# main.net
KiCad netlist of a schematic drawn in EAGLE
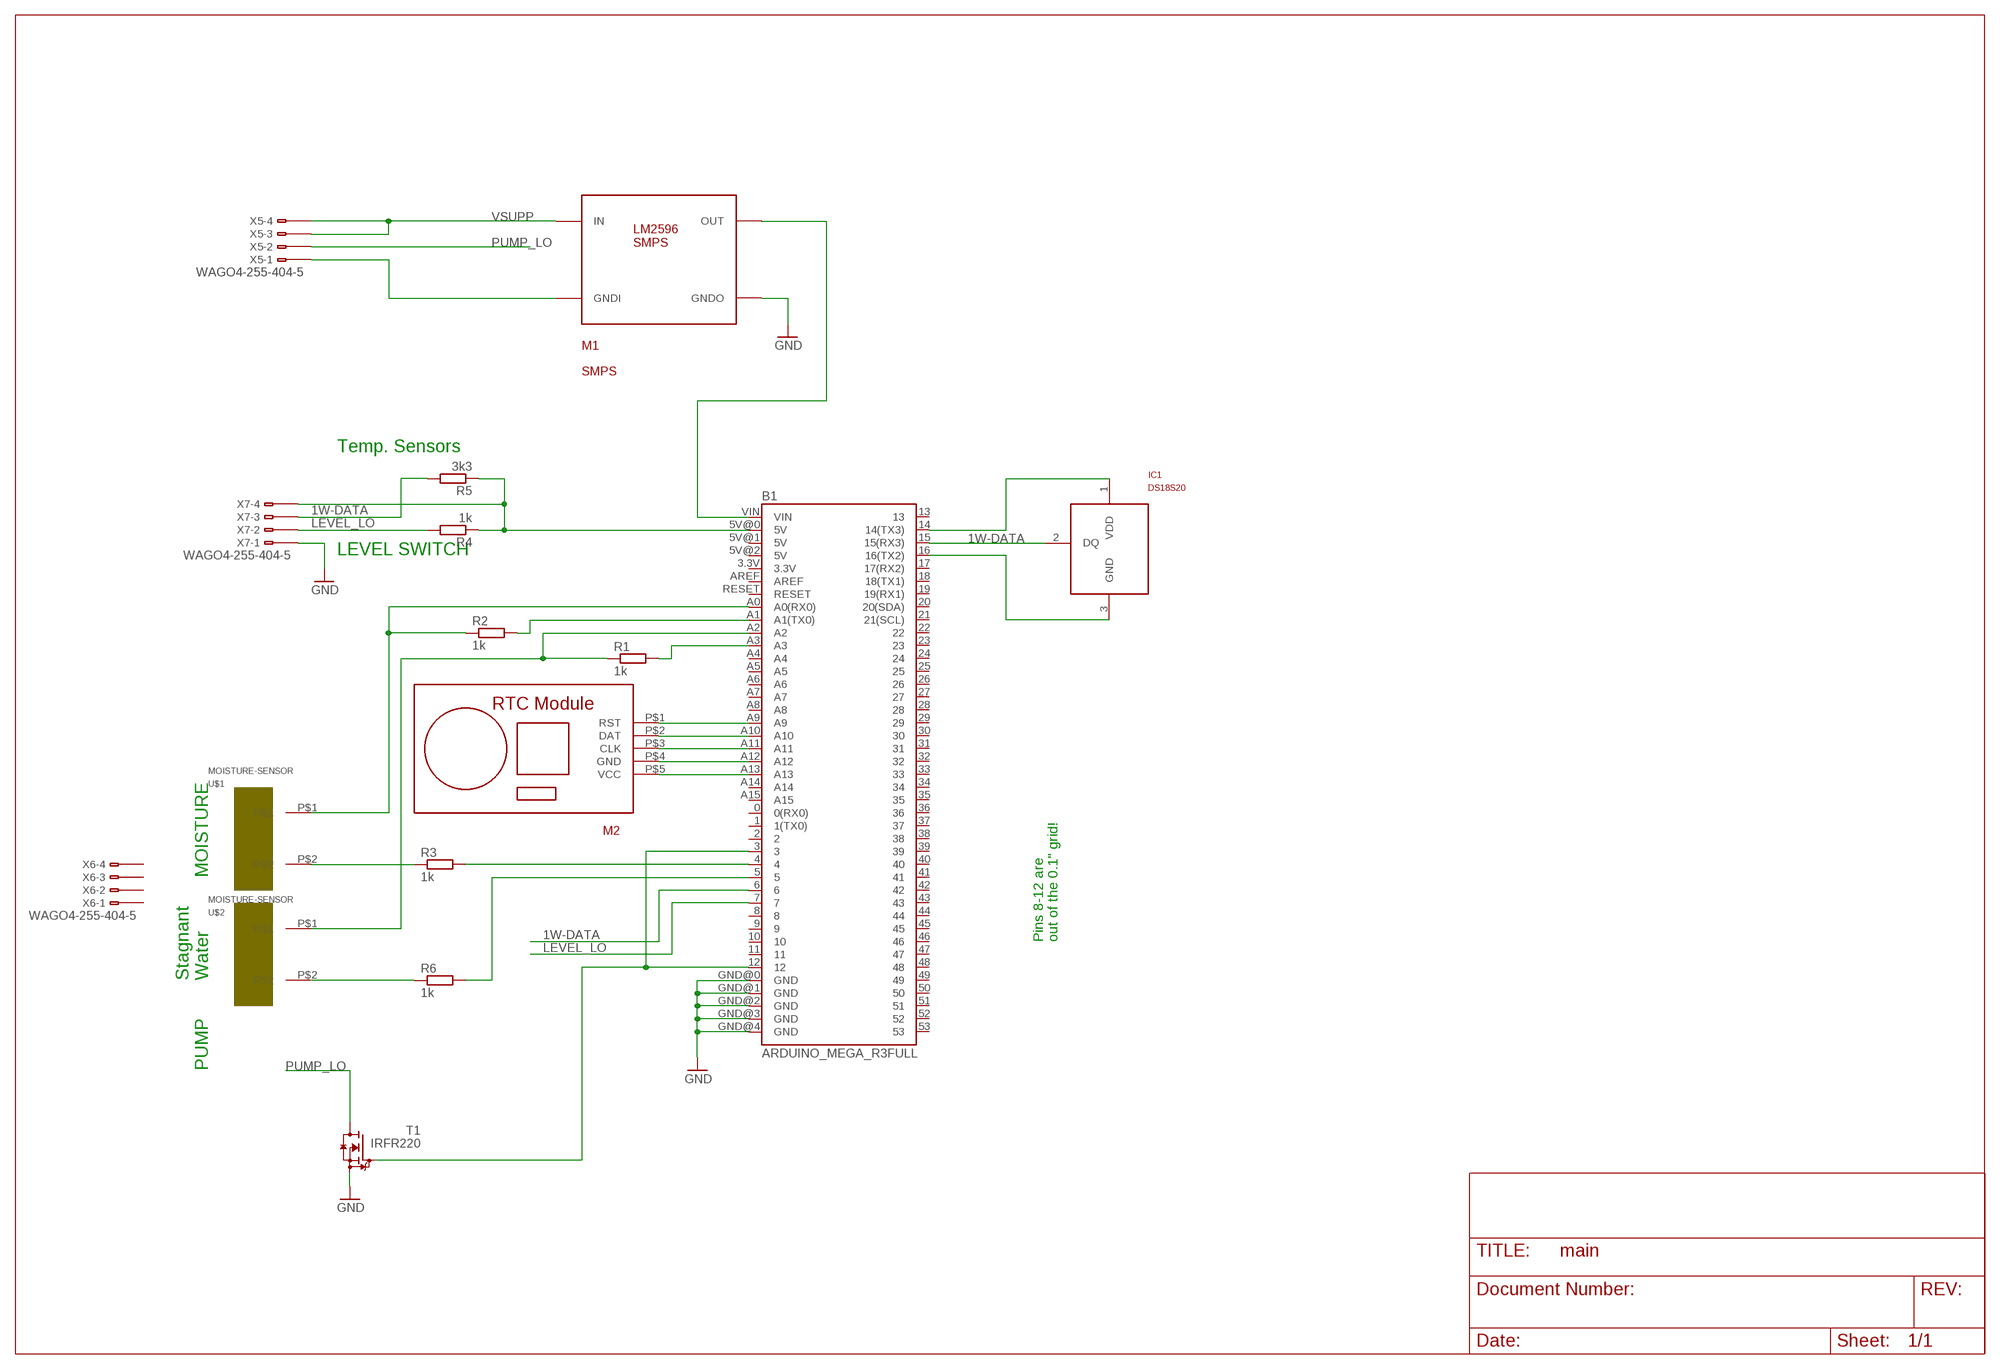
[diagram p0: schematic, sheet 1]

(export (version "E")
  (design (tool "Eeschema 10.0.6"))
  (components
    (comp (ref "B1")
      (value "ARDUINO_MEGA_R3FULL")
      (footprint "eagle-import:ARDUINO_MEGA")
      (libsource (lib "eagle-import") (part "ARDUINO_MEGA_R3FULL"))
    )
    (comp (ref "IC1")
      (value "DS18S20")
      (footprint "eagle-import:TO92-")
      (libsource (lib "eagle-import") (part "DS1820"))
    )
    (comp (ref "M1")
      (value "SMPS")
      (footprint "eagle-import:SMPS-1")
      (libsource (lib "eagle-import") (part "SMPS"))
    )
    (comp (ref "M2")
      (value "DS1302-MODULE")
      (footprint "eagle-import:DS1302-MOD")
      (libsource (lib "eagle-import") (part "DS1302-MODULE"))
    )
    (comp (ref "R1")
      (value "1k")
      (footprint "eagle-import:R0805")
      (libsource (lib "eagle-import") (part "R-EU_R0805"))
    )
    (comp (ref "R2")
      (value "1k")
      (footprint "eagle-import:R0805")
      (libsource (lib "eagle-import") (part "R-EU_R0805"))
    )
    (comp (ref "R3")
      (value "1k")
      (footprint "eagle-import:R0805")
      (libsource (lib "eagle-import") (part "R-EU_R0805"))
    )
    (comp (ref "R4")
      (value "1k")
      (footprint "eagle-import:R0805")
      (libsource (lib "eagle-import") (part "R-EU_R0805"))
    )
    (comp (ref "R5")
      (value "3k3")
      (footprint "eagle-import:R0805")
      (libsource (lib "eagle-import") (part "R-EU_R0805"))
    )
    (comp (ref "R6")
      (value "1k")
      (footprint "eagle-import:R0805")
      (libsource (lib "eagle-import") (part "R-EU_R0805"))
    )
    (comp (ref "T1")
      (value "IRFR220")
      (footprint "eagle-import:TO252")
      (libsource (lib "eagle-import") (part "IRFR220"))
    )
    (comp (ref "U$1")
      (value "MOISTURE-SENSOR")
      (footprint "eagle-import:MOISTURE-SENSOR")
      (libsource (lib "eagle-import") (part "MOISTURE-SENSOR"))
    )
    (comp (ref "U$2")
      (value "MOISTURE-SENSOR")
      (footprint "eagle-import:MOISTURE-SENSOR")
      (libsource (lib "eagle-import") (part "MOISTURE-SENSOR"))
    )
    (comp (ref "X5")
      (value "WAGO4-255-404-5")
      (footprint "eagle-import:255-404-5")
      (fields (field (name "MPN") "255-404"))
      (libsource (lib "eagle-import") (part "WAGO4-255-404-5"))
    )
    (comp (ref "X6")
      (value "WAGO4-255-404-5")
      (footprint "eagle-import:255-404-5")
      (fields (field (name "MPN") "255-404"))
      (libsource (lib "eagle-import") (part "WAGO4-255-404-5"))
    )
    (comp (ref "X7")
      (value "WAGO4-255-404-5")
      (footprint "eagle-import:255-404-5")
      (fields (field (name "MPN") "255-404"))
      (libsource (lib "eagle-import") (part "WAGO4-255-404-5"))
    )
  )
  (nets
    (net (code "1") (name "/1W-DATA") (class "Default")
      (node (ref "B1") (pin "15") (pinfunction "15(RX3)_15") (pintype "bidirectional"))
      (node (ref "B1") (pin "6") (pinfunction "6_6") (pintype "bidirectional"))
      (node (ref "IC1") (pin "2") (pinfunction "DQ_2") (pintype "bidirectional"))
      (node (ref "R5") (pin "2") (pinfunction "2_2") (pintype "passive"))
      (node (ref "X7") (pin "B3") (pinfunction "B1_B3") (pintype "passive"))
    )
    (net (code "2") (name "/LEVEL_LO") (class "Default")
      (node (ref "B1") (pin "7") (pinfunction "7_7") (pintype "bidirectional"))
      (node (ref "R4") (pin "2") (pinfunction "2_2") (pintype "passive"))
      (node (ref "X7") (pin "B2") (pinfunction "B1_B2") (pintype "passive"))
    )
    (net (code "3") (name "/PUMP_LO") (class "Default")
      (node (ref "T1") (pin "3") (pinfunction "D_3") (pintype "passive"))
      (node (ref "X5") (pin "B2") (pinfunction "B1_B2") (pintype "passive"))
    )
    (net (code "4") (name "/VSUPP") (class "Default")
      (node (ref "M1") (pin "P$3") (pinfunction "IN_P$3") (pintype "input"))
      (node (ref "M1") (pin "P$4") (pinfunction "IN_P$4") (pintype "input"))
      (node (ref "X5") (pin "B3") (pinfunction "B1_B3") (pintype "passive"))
      (node (ref "X5") (pin "B4") (pinfunction "B1_B4") (pintype "passive"))
    )
    (net (code "5") (name "GND") (class "Default")
      (node (ref "B1") (pin "GND@0") (pinfunction "GND_GND@0") (pintype "bidirectional"))
      (node (ref "B1") (pin "GND@1") (pinfunction "GND_GND@1") (pintype "bidirectional"))
      (node (ref "B1") (pin "GND@2") (pinfunction "GND_GND@2") (pintype "bidirectional"))
      (node (ref "B1") (pin "GND@3") (pinfunction "GND_GND@3") (pintype "bidirectional"))
      (node (ref "B1") (pin "GND@4") (pinfunction "GND_GND@4") (pintype "bidirectional"))
      (node (ref "M1") (pin "P$5") (pinfunction "GNDO_P$5") (pintype "output"))
      (node (ref "M1") (pin "P$6") (pinfunction "GNDO_P$6") (pintype "output"))
      (node (ref "T1") (pin "2") (pinfunction "S_2") (pintype "passive"))
      (node (ref "X7") (pin "B1") (pinfunction "B1_B1") (pintype "passive"))
    )
    (net (code "6") (name "Net-(B1-14(TX3))") (class "Default")
      (node (ref "B1") (pin "14") (pinfunction "14(TX3)_14") (pintype "bidirectional"))
      (node (ref "IC1") (pin "1") (pinfunction "VDD_1") (pintype "bidirectional"))
    )
    (net (code "7") (name "Net-(B1-16(TX2))") (class "Default")
      (node (ref "B1") (pin "16") (pinfunction "16(TX2)_16") (pintype "bidirectional"))
      (node (ref "IC1") (pin "3") (pinfunction "GND_3") (pintype "bidirectional"))
    )
    (net (code "8") (name "Net-(B1-A0(RX0))") (class "Default")
      (node (ref "B1") (pin "A0") (pinfunction "A0(RX0)_A0") (pintype "bidirectional"))
      (node (ref "R2") (pin "1") (pinfunction "1_1") (pintype "passive"))
      (node (ref "U$1") (pin "P$1") (pinfunction "P$1_P$1") (pintype "bidirectional"))
    )
    (net (code "9") (name "Net-(B1-A1(TX0))") (class "Default")
      (node (ref "B1") (pin "A1") (pinfunction "A1(TX0)_A1") (pintype "bidirectional"))
      (node (ref "R2") (pin "2") (pinfunction "2_2") (pintype "passive"))
    )
    (net (code "10") (name "Net-(B1-Pad4)") (class "Default")
      (node (ref "B1") (pin "4") (pinfunction "4_4") (pintype "bidirectional"))
      (node (ref "R3") (pin "2") (pinfunction "2_2") (pintype "passive"))
    )
    (net (code "11") (name "Net-(B1-Pad5)") (class "Default")
      (node (ref "B1") (pin "5") (pinfunction "5_5") (pintype "bidirectional"))
      (node (ref "R6") (pin "2") (pinfunction "2_2") (pintype "passive"))
    )
    (net (code "12") (name "Net-(B1-PadA2)") (class "Default")
      (node (ref "B1") (pin "A2") (pinfunction "A2_A2") (pintype "bidirectional"))
      (node (ref "R1") (pin "1") (pinfunction "1_1") (pintype "passive"))
      (node (ref "U$2") (pin "P$1") (pinfunction "P$1_P$1") (pintype "bidirectional"))
    )
    (net (code "13") (name "Net-(B1-PadA3)") (class "Default")
      (node (ref "B1") (pin "A3") (pinfunction "A3_A3") (pintype "bidirectional"))
      (node (ref "R1") (pin "2") (pinfunction "2_2") (pintype "passive"))
    )
    (net (code "14") (name "Net-(B1-PadVIN)") (class "Default")
      (node (ref "B1") (pin "VIN") (pinfunction "VIN_VIN") (pintype "bidirectional"))
      (node (ref "M1") (pin "P$7") (pinfunction "OUT_P$7") (pintype "output"))
      (node (ref "M1") (pin "P$8") (pinfunction "OUT_P$8") (pintype "output"))
    )
    (net (code "15") (name "Net-(M1-GNDI-PadP$1)") (class "Default")
      (node (ref "M1") (pin "P$1") (pinfunction "GNDI_P$1") (pintype "input"))
      (node (ref "M1") (pin "P$2") (pinfunction "GNDI_P$2") (pintype "input"))
      (node (ref "X5") (pin "B1") (pinfunction "B1_B1") (pintype "passive"))
    )
    (net (code "16") (name "Net-(M2-CLK)") (class "Default")
      (node (ref "B1") (pin "A11") (pinfunction "A11_A11") (pintype "bidirectional"))
      (node (ref "M2") (pin "P$3") (pinfunction "CLK_P$3") (pintype "bidirectional"))
    )
    (net (code "17") (name "Net-(M2-DAT)") (class "Default")
      (node (ref "B1") (pin "A10") (pinfunction "A10_A10") (pintype "bidirectional"))
      (node (ref "M2") (pin "P$2") (pinfunction "DAT_P$2") (pintype "bidirectional"))
    )
    (net (code "18") (name "Net-(M2-GND)") (class "Default")
      (node (ref "B1") (pin "A12") (pinfunction "A12_A12") (pintype "bidirectional"))
      (node (ref "M2") (pin "P$4") (pinfunction "GND_P$4") (pintype "bidirectional"))
    )
    (net (code "19") (name "Net-(M2-RST)") (class "Default")
      (node (ref "B1") (pin "A9") (pinfunction "A9_A9") (pintype "bidirectional"))
      (node (ref "M2") (pin "P$1") (pinfunction "RST_P$1") (pintype "bidirectional"))
    )
    (net (code "20") (name "Net-(M2-VCC)") (class "Default")
      (node (ref "B1") (pin "A13") (pinfunction "A13_A13") (pintype "bidirectional"))
      (node (ref "M2") (pin "P$5") (pinfunction "VCC_P$5") (pintype "bidirectional"))
    )
    (net (code "21") (name "Net-(R3-Pad1)") (class "Default")
      (node (ref "R3") (pin "1") (pinfunction "1_1") (pintype "passive"))
      (node (ref "U$1") (pin "P$2") (pinfunction "P$2_P$2") (pintype "bidirectional"))
    )
    (net (code "22") (name "Net-(R6-Pad1)") (class "Default")
      (node (ref "R6") (pin "1") (pinfunction "1_1") (pintype "passive"))
      (node (ref "U$2") (pin "P$2") (pinfunction "P$2_P$2") (pintype "bidirectional"))
    )
    (net (code "23") (name "Net-(T1-G)") (class "Default")
      (node (ref "B1") (pin "12") (pinfunction "12_12") (pintype "bidirectional"))
      (node (ref "B1") (pin "3") (pinfunction "3_3") (pintype "bidirectional"))
      (node (ref "T1") (pin "1") (pinfunction "G_1") (pintype "passive"))
    )
    (net (code "24") (name "Net-(X7D-B1)") (class "Default")
      (node (ref "B1") (pin "5V@0") (pinfunction "5V_5V@0") (pintype "bidirectional"))
      (node (ref "R4") (pin "1") (pinfunction "1_1") (pintype "passive"))
      (node (ref "R5") (pin "1") (pinfunction "1_1") (pintype "passive"))
      (node (ref "X7") (pin "B4") (pinfunction "B1_B4") (pintype "passive"))
    )
    (net (code "25") (name "unconnected-(B1-0(RX0)-Pad0)") (class "Default")
      (node (ref "B1") (pin "0") (pinfunction "0(RX0)_0") (pintype "bidirectional"))
    )
    (net (code "26") (name "unconnected-(B1-1(TX0)-Pad1)") (class "Default")
      (node (ref "B1") (pin "1") (pinfunction "1(TX0)_1") (pintype "bidirectional"))
    )
    (net (code "27") (name "unconnected-(B1-5V-Pad5V@1)") (class "Default")
      (node (ref "B1") (pin "5V@1") (pinfunction "5V_5V@1") (pintype "bidirectional"))
    )
    (net (code "28") (name "unconnected-(B1-5V-Pad5V@2)") (class "Default")
      (node (ref "B1") (pin "5V@2") (pinfunction "5V_5V@2") (pintype "bidirectional"))
    )
    (net (code "29") (name "unconnected-(B1-17(RX2)-Pad17)") (class "Default")
      (node (ref "B1") (pin "17") (pinfunction "17(RX2)_17") (pintype "bidirectional"))
    )
    (net (code "30") (name "unconnected-(B1-18(TX1)-Pad18)") (class "Default")
      (node (ref "B1") (pin "18") (pinfunction "18(TX1)_18") (pintype "bidirectional"))
    )
    (net (code "31") (name "unconnected-(B1-19(RX1)-Pad19)") (class "Default")
      (node (ref "B1") (pin "19") (pinfunction "19(RX1)_19") (pintype "bidirectional"))
    )
    (net (code "32") (name "unconnected-(B1-20(SDA)-Pad20)") (class "Default")
      (node (ref "B1") (pin "20") (pinfunction "20(SDA)_20") (pintype "bidirectional"))
    )
    (net (code "33") (name "unconnected-(B1-21(SCL)-Pad21)") (class "Default")
      (node (ref "B1") (pin "21") (pinfunction "21(SCL)_21") (pintype "bidirectional"))
    )
    (net (code "34") (name "unconnected-(B1-Pad2)") (class "Default")
      (node (ref "B1") (pin "2") (pinfunction "2_2") (pintype "bidirectional"))
    )
    (net (code "35") (name "unconnected-(B1-Pad3.3V)") (class "Default")
      (node (ref "B1") (pin "3.3V") (pinfunction "3.3V_3.3V") (pintype "bidirectional"))
    )
    (net (code "36") (name "unconnected-(B1-Pad8)") (class "Default")
      (node (ref "B1") (pin "8") (pinfunction "8_8") (pintype "bidirectional"))
    )
    (net (code "37") (name "unconnected-(B1-Pad9)") (class "Default")
      (node (ref "B1") (pin "9") (pinfunction "9_9") (pintype "bidirectional"))
    )
    (net (code "38") (name "unconnected-(B1-Pad10)") (class "Default")
      (node (ref "B1") (pin "10") (pinfunction "10_10") (pintype "bidirectional"))
    )
    (net (code "39") (name "unconnected-(B1-Pad11)") (class "Default")
      (node (ref "B1") (pin "11") (pinfunction "11_11") (pintype "bidirectional"))
    )
    (net (code "40") (name "unconnected-(B1-Pad13)") (class "Default")
      (node (ref "B1") (pin "13") (pinfunction "13_13") (pintype "bidirectional"))
    )
    (net (code "41") (name "unconnected-(B1-Pad22)") (class "Default")
      (node (ref "B1") (pin "22") (pinfunction "22_22") (pintype "bidirectional"))
    )
    (net (code "42") (name "unconnected-(B1-Pad23)") (class "Default")
      (node (ref "B1") (pin "23") (pinfunction "23_23") (pintype "bidirectional"))
    )
    (net (code "43") (name "unconnected-(B1-Pad24)") (class "Default")
      (node (ref "B1") (pin "24") (pinfunction "24_24") (pintype "bidirectional"))
    )
    (net (code "44") (name "unconnected-(B1-Pad25)") (class "Default")
      (node (ref "B1") (pin "25") (pinfunction "25_25") (pintype "bidirectional"))
    )
    (net (code "45") (name "unconnected-(B1-Pad26)") (class "Default")
      (node (ref "B1") (pin "26") (pinfunction "26_26") (pintype "bidirectional"))
    )
    (net (code "46") (name "unconnected-(B1-Pad27)") (class "Default")
      (node (ref "B1") (pin "27") (pinfunction "27_27") (pintype "bidirectional"))
    )
    (net (code "47") (name "unconnected-(B1-Pad28)") (class "Default")
      (node (ref "B1") (pin "28") (pinfunction "28_28") (pintype "bidirectional"))
    )
    (net (code "48") (name "unconnected-(B1-Pad29)") (class "Default")
      (node (ref "B1") (pin "29") (pinfunction "29_29") (pintype "bidirectional"))
    )
    (net (code "49") (name "unconnected-(B1-Pad30)") (class "Default")
      (node (ref "B1") (pin "30") (pinfunction "30_30") (pintype "bidirectional"))
    )
    (net (code "50") (name "unconnected-(B1-Pad31)") (class "Default")
      (node (ref "B1") (pin "31") (pinfunction "31_31") (pintype "bidirectional"))
    )
    (net (code "51") (name "unconnected-(B1-Pad32)") (class "Default")
      (node (ref "B1") (pin "32") (pinfunction "32_32") (pintype "bidirectional"))
    )
    (net (code "52") (name "unconnected-(B1-Pad33)") (class "Default")
      (node (ref "B1") (pin "33") (pinfunction "33_33") (pintype "bidirectional"))
    )
    (net (code "53") (name "unconnected-(B1-Pad34)") (class "Default")
      (node (ref "B1") (pin "34") (pinfunction "34_34") (pintype "bidirectional"))
    )
    (net (code "54") (name "unconnected-(B1-Pad35)") (class "Default")
      (node (ref "B1") (pin "35") (pinfunction "35_35") (pintype "bidirectional"))
    )
    (net (code "55") (name "unconnected-(B1-Pad36)") (class "Default")
      (node (ref "B1") (pin "36") (pinfunction "36_36") (pintype "bidirectional"))
    )
    (net (code "56") (name "unconnected-(B1-Pad37)") (class "Default")
      (node (ref "B1") (pin "37") (pinfunction "37_37") (pintype "bidirectional"))
    )
    (net (code "57") (name "unconnected-(B1-Pad38)") (class "Default")
      (node (ref "B1") (pin "38") (pinfunction "38_38") (pintype "bidirectional"))
    )
    (net (code "58") (name "unconnected-(B1-Pad39)") (class "Default")
      (node (ref "B1") (pin "39") (pinfunction "39_39") (pintype "bidirectional"))
    )
    (net (code "59") (name "unconnected-(B1-Pad40)") (class "Default")
      (node (ref "B1") (pin "40") (pinfunction "40_40") (pintype "bidirectional"))
    )
    (net (code "60") (name "unconnected-(B1-Pad41)") (class "Default")
      (node (ref "B1") (pin "41") (pinfunction "41_41") (pintype "bidirectional"))
    )
    (net (code "61") (name "unconnected-(B1-Pad42)") (class "Default")
      (node (ref "B1") (pin "42") (pinfunction "42_42") (pintype "bidirectional"))
    )
    (net (code "62") (name "unconnected-(B1-Pad43)") (class "Default")
      (node (ref "B1") (pin "43") (pinfunction "43_43") (pintype "bidirectional"))
    )
    (net (code "63") (name "unconnected-(B1-Pad44)") (class "Default")
      (node (ref "B1") (pin "44") (pinfunction "44_44") (pintype "bidirectional"))
    )
    (net (code "64") (name "unconnected-(B1-Pad45)") (class "Default")
      (node (ref "B1") (pin "45") (pinfunction "45_45") (pintype "bidirectional"))
    )
    (net (code "65") (name "unconnected-(B1-Pad46)") (class "Default")
      (node (ref "B1") (pin "46") (pinfunction "46_46") (pintype "bidirectional"))
    )
    (net (code "66") (name "unconnected-(B1-Pad47)") (class "Default")
      (node (ref "B1") (pin "47") (pinfunction "47_47") (pintype "bidirectional"))
    )
    (net (code "67") (name "unconnected-(B1-Pad48)") (class "Default")
      (node (ref "B1") (pin "48") (pinfunction "48_48") (pintype "bidirectional"))
    )
    (net (code "68") (name "unconnected-(B1-Pad49)") (class "Default")
      (node (ref "B1") (pin "49") (pinfunction "49_49") (pintype "bidirectional"))
    )
    (net (code "69") (name "unconnected-(B1-Pad50)") (class "Default")
      (node (ref "B1") (pin "50") (pinfunction "50_50") (pintype "bidirectional"))
    )
    (net (code "70") (name "unconnected-(B1-Pad51)") (class "Default")
      (node (ref "B1") (pin "51") (pinfunction "51_51") (pintype "bidirectional"))
    )
    (net (code "71") (name "unconnected-(B1-Pad52)") (class "Default")
      (node (ref "B1") (pin "52") (pinfunction "52_52") (pintype "bidirectional"))
    )
    (net (code "72") (name "unconnected-(B1-Pad53)") (class "Default")
      (node (ref "B1") (pin "53") (pinfunction "53_53") (pintype "bidirectional"))
    )
    (net (code "73") (name "unconnected-(B1-PadA4)") (class "Default")
      (node (ref "B1") (pin "A4") (pinfunction "A4_A4") (pintype "bidirectional"))
    )
    (net (code "74") (name "unconnected-(B1-PadA5)") (class "Default")
      (node (ref "B1") (pin "A5") (pinfunction "A5_A5") (pintype "bidirectional"))
    )
    (net (code "75") (name "unconnected-(B1-PadA6)") (class "Default")
      (node (ref "B1") (pin "A6") (pinfunction "A6_A6") (pintype "bidirectional"))
    )
    (net (code "76") (name "unconnected-(B1-PadA7)") (class "Default")
      (node (ref "B1") (pin "A7") (pinfunction "A7_A7") (pintype "bidirectional"))
    )
    (net (code "77") (name "unconnected-(B1-PadA8)") (class "Default")
      (node (ref "B1") (pin "A8") (pinfunction "A8_A8") (pintype "bidirectional"))
    )
    (net (code "78") (name "unconnected-(B1-PadA14)") (class "Default")
      (node (ref "B1") (pin "A14") (pinfunction "A14_A14") (pintype "bidirectional"))
    )
    (net (code "79") (name "unconnected-(B1-PadA15)") (class "Default")
      (node (ref "B1") (pin "A15") (pinfunction "A15_A15") (pintype "bidirectional"))
    )
    (net (code "80") (name "unconnected-(B1-PadAREF)") (class "Default")
      (node (ref "B1") (pin "AREF") (pinfunction "AREF_AREF") (pintype "bidirectional"))
    )
    (net (code "81") (name "unconnected-(B1-PadRESET)") (class "Default")
      (node (ref "B1") (pin "RESET") (pinfunction "RESET_RESET") (pintype "bidirectional"))
    )
    (net (code "82") (name "unconnected-(X5-PadA1)") (class "Default")
      (node (ref "X5") (pin "A1") (pinfunction "A1_A1") (pintype "passive"))
    )
    (net (code "83") (name "unconnected-(X5B-A1-PadA2)") (class "Default")
      (node (ref "X5") (pin "A2") (pinfunction "A1_A2") (pintype "passive"))
    )
    (net (code "84") (name "unconnected-(X5C-A1-PadA3)") (class "Default")
      (node (ref "X5") (pin "A3") (pinfunction "A1_A3") (pintype "passive"))
    )
    (net (code "85") (name "unconnected-(X5D-A1-PadA4)") (class "Default")
      (node (ref "X5") (pin "A4") (pinfunction "A1_A4") (pintype "passive"))
    )
    (net (code "86") (name "unconnected-(X6-PadA1)") (class "Default")
      (node (ref "X6") (pin "A1") (pinfunction "A1_A1") (pintype "passive"))
    )
    (net (code "87") (name "unconnected-(X6-PadB1)") (class "Default")
      (node (ref "X6") (pin "B1") (pinfunction "B1_B1") (pintype "passive"))
    )
    (net (code "88") (name "unconnected-(X6B-A1-PadA2)") (class "Default")
      (node (ref "X6") (pin "A2") (pinfunction "A1_A2") (pintype "passive"))
    )
    (net (code "89") (name "unconnected-(X6B-B1-PadB2)") (class "Default")
      (node (ref "X6") (pin "B2") (pinfunction "B1_B2") (pintype "passive"))
    )
    (net (code "90") (name "unconnected-(X6C-A1-PadA3)") (class "Default")
      (node (ref "X6") (pin "A3") (pinfunction "A1_A3") (pintype "passive"))
    )
    (net (code "91") (name "unconnected-(X6C-B1-PadB3)") (class "Default")
      (node (ref "X6") (pin "B3") (pinfunction "B1_B3") (pintype "passive"))
    )
    (net (code "92") (name "unconnected-(X6D-A1-PadA4)") (class "Default")
      (node (ref "X6") (pin "A4") (pinfunction "A1_A4") (pintype "passive"))
    )
    (net (code "93") (name "unconnected-(X6D-B1-PadB4)") (class "Default")
      (node (ref "X6") (pin "B4") (pinfunction "B1_B4") (pintype "passive"))
    )
    (net (code "94") (name "unconnected-(X7-PadA1)") (class "Default")
      (node (ref "X7") (pin "A1") (pinfunction "A1_A1") (pintype "passive"))
    )
    (net (code "95") (name "unconnected-(X7B-A1-PadA2)") (class "Default")
      (node (ref "X7") (pin "A2") (pinfunction "A1_A2") (pintype "passive"))
    )
    (net (code "96") (name "unconnected-(X7C-A1-PadA3)") (class "Default")
      (node (ref "X7") (pin "A3") (pinfunction "A1_A3") (pintype "passive"))
    )
    (net (code "97") (name "unconnected-(X7D-A1-PadA4)") (class "Default")
      (node (ref "X7") (pin "A4") (pinfunction "A1_A4") (pintype "passive"))
    )
  )
)
